# BMP280-Breakout_v11.net
KiCad netlist of a schematic drawn in EAGLE
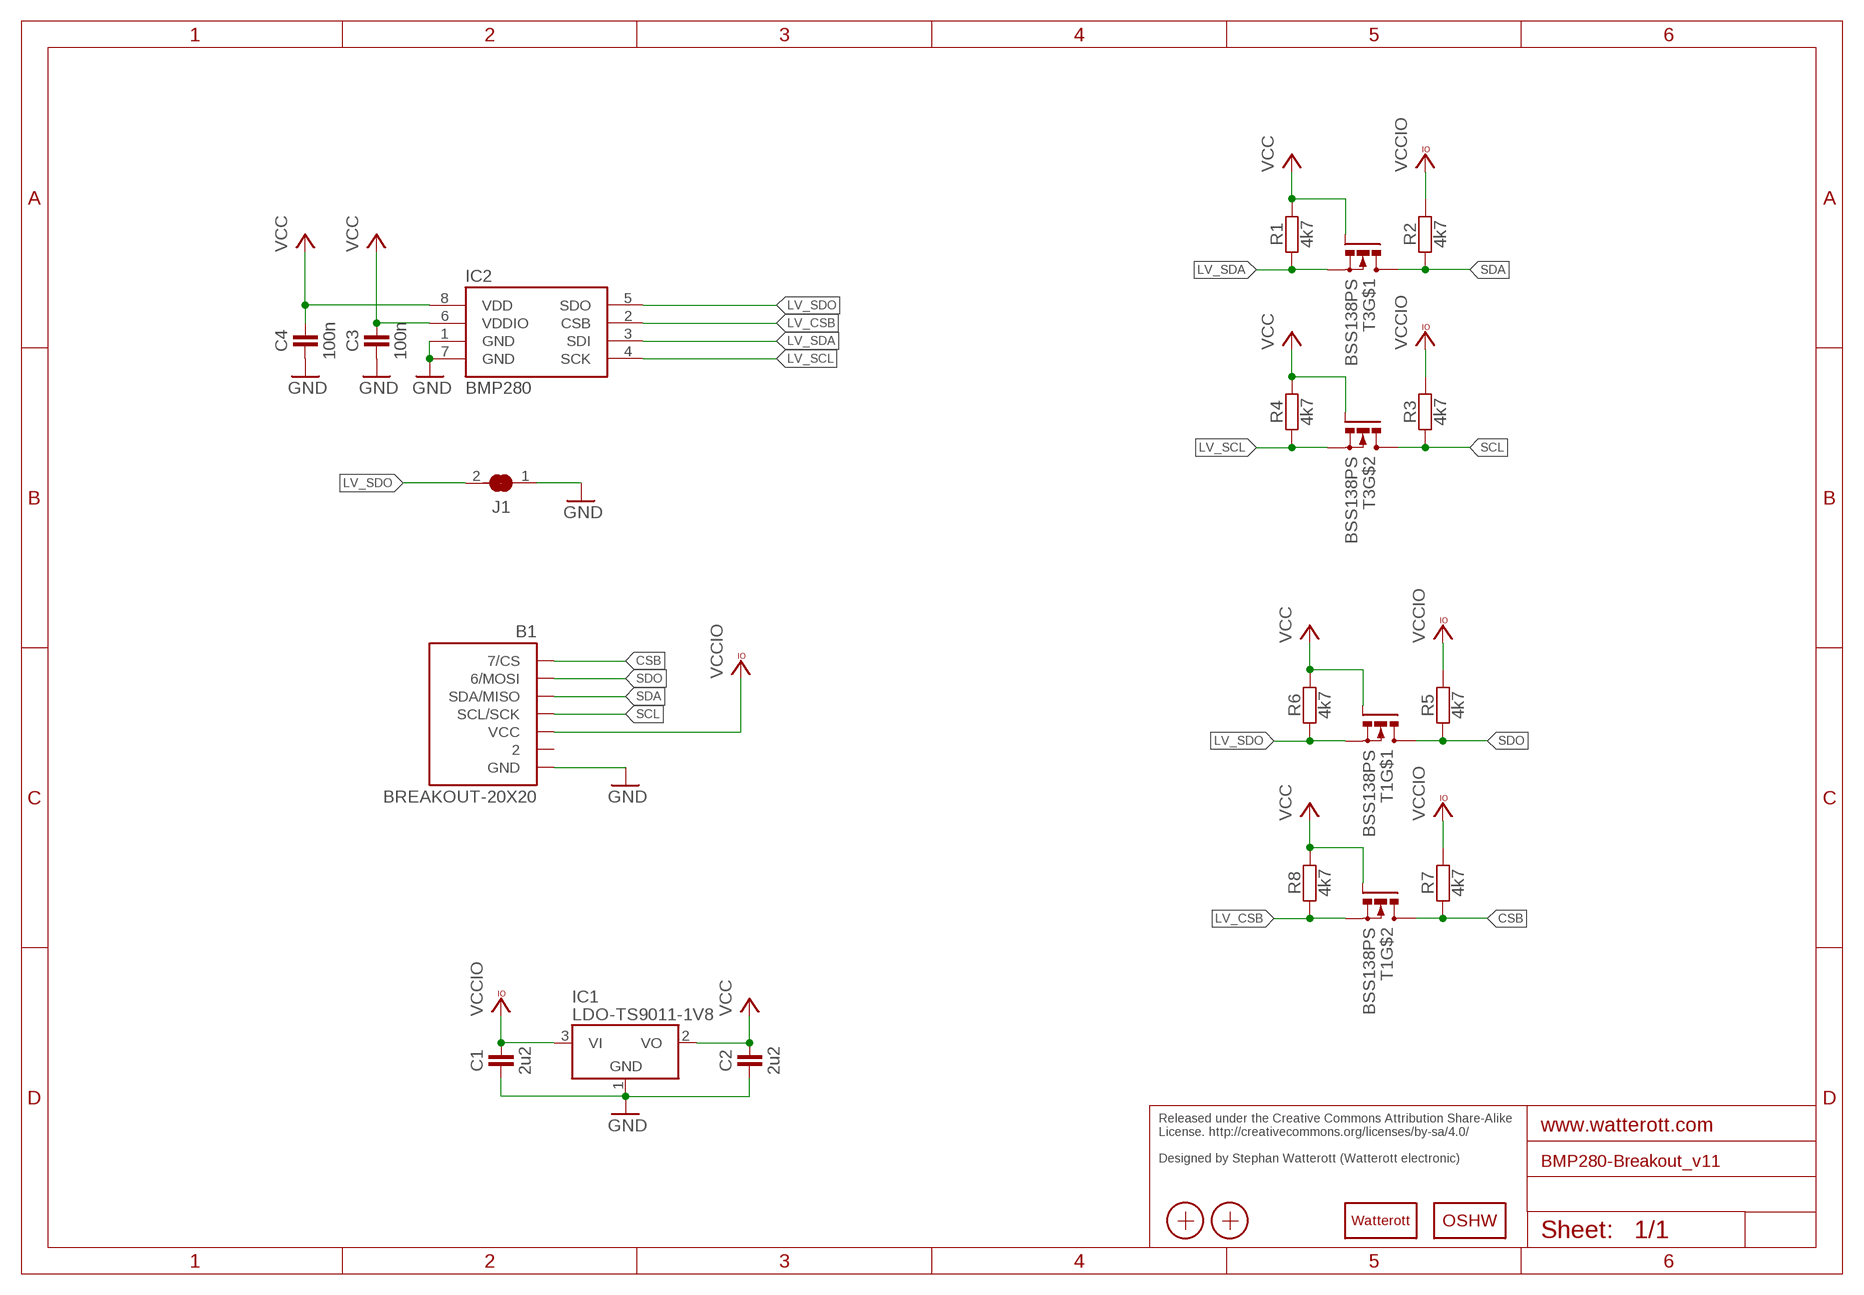
[diagram p0: schematic, sheet 1]

(export (version "E")
  (design (tool "Eeschema 10.0.6"))
  (components
    (comp (ref "B1")
      (value "BREAKOUT-20X20")
      (footprint "eagle-import:BREAKOUT-20X20")
      (libsource (lib "eagle-import") (part "BREAKOUT-20X20"))
    )
    (comp (ref "C1")
      (value "2u2")
      (footprint "eagle-import:R0402")
      (libsource (lib "eagle-import") (part "CAPACITOR-C0402"))
    )
    (comp (ref "C2")
      (value "2u2")
      (footprint "eagle-import:R0402")
      (libsource (lib "eagle-import") (part "CAPACITOR-C0402"))
    )
    (comp (ref "C3")
      (value "100n")
      (footprint "eagle-import:R0402")
      (libsource (lib "eagle-import") (part "CAPACITOR-C0402"))
    )
    (comp (ref "C4")
      (value "100n")
      (footprint "eagle-import:R0402")
      (libsource (lib "eagle-import") (part "CAPACITOR-C0402"))
    )
    (comp (ref "IC1")
      (value "LDO-TS9011-1V8")
      (footprint "eagle-import:SOT23")
      (libsource (lib "eagle-import") (part "LDO-TS9011-3V3"))
    )
    (comp (ref "IC2")
      (value "BMP280")
      (footprint "eagle-import:LGA")
      (libsource (lib "eagle-import") (part "BMP280"))
    )
    (comp (ref "J1")
      (value "JUMPER2")
      (footprint "eagle-import:JUMPER2")
      (libsource (lib "eagle-import") (part "JUMPER2"))
    )
    (comp (ref "LOGO1")
      (value "LOGO-S_PLACE_M")
      (footprint "eagle-import:SPARK_TPLACE_M")
      (libsource (lib "eagle-import") (part "LOGO-S_PLACE_M"))
    )
    (comp (ref "LOGO2")
      (value "OSHW_LOGOX0070")
      (footprint "eagle-import:OSHW_6X70")
      (libsource (lib "eagle-import") (part "OSHW_LOGOX0070"))
    )
    (comp (ref "R1")
      (value "4k7")
      (footprint "eagle-import:R0402")
      (libsource (lib "eagle-import") (part "RESISTOR-R0402"))
    )
    (comp (ref "R2")
      (value "4k7")
      (footprint "eagle-import:R0402")
      (libsource (lib "eagle-import") (part "RESISTOR-R0402"))
    )
    (comp (ref "R3")
      (value "4k7")
      (footprint "eagle-import:R0402")
      (libsource (lib "eagle-import") (part "RESISTOR-R0402"))
    )
    (comp (ref "R4")
      (value "4k7")
      (footprint "eagle-import:R0402")
      (libsource (lib "eagle-import") (part "RESISTOR-R0402"))
    )
    (comp (ref "R5")
      (value "4k7")
      (footprint "eagle-import:R0402")
      (libsource (lib "eagle-import") (part "RESISTOR-R0402"))
    )
    (comp (ref "R6")
      (value "4k7")
      (footprint "eagle-import:R0402")
      (libsource (lib "eagle-import") (part "RESISTOR-R0402"))
    )
    (comp (ref "R7")
      (value "4k7")
      (footprint "eagle-import:R0402")
      (libsource (lib "eagle-import") (part "RESISTOR-R0402"))
    )
    (comp (ref "R8")
      (value "4k7")
      (footprint "eagle-import:R0402")
      (libsource (lib "eagle-import") (part "RESISTOR-R0402"))
    )
    (comp (ref "T1")
      (value "BSS138PS")
      (footprint "eagle-import:SOT363")
      (libsource (lib "eagle-import") (part "BSS138PS"))
    )
    (comp (ref "T3")
      (value "BSS138PS")
      (footprint "eagle-import:SOT363")
      (libsource (lib "eagle-import") (part "BSS138PS"))
    )
    (comp (ref "X1")
      (value "PASSER-07")
      (footprint "eagle-import:PASSER_07MM")
      (libsource (lib "eagle-import") (part "PASSER-07"))
    )
    (comp (ref "X2")
      (value "PASSER-07")
      (footprint "eagle-import:PASSER_07MM")
      (libsource (lib "eagle-import") (part "PASSER-07"))
    )
  )
  (nets
    (net (code "1") (name "CSB") (class "Default")
      (node (ref "B1") (pin "CS") (pinfunction "7/CS_CS") (pintype "bidirectional"))
      (node (ref "R7") (pin "1") (pinfunction "1_1") (pintype "passive"))
      (node (ref "T1") (pin "3") (pinfunction "D_3") (pintype "passive"))
    )
    (net (code "2") (name "GND") (class "Default")
      (node (ref "B1") (pin "GND") (pinfunction "GND_GND") (pintype "power_in"))
      (node (ref "C1") (pin "1") (pinfunction "1_1") (pintype "passive"))
      (node (ref "C2") (pin "1") (pinfunction "1_1") (pintype "passive"))
      (node (ref "C3") (pin "1") (pinfunction "1_1") (pintype "passive"))
      (node (ref "C4") (pin "1") (pinfunction "1_1") (pintype "passive"))
      (node (ref "IC1") (pin "1") (pinfunction "GND_1") (pintype "passive"))
      (node (ref "IC2") (pin "1") (pinfunction "GND_1") (pintype "power_in"))
      (node (ref "IC2") (pin "7") (pinfunction "GND_7") (pintype "power_in"))
      (node (ref "J1") (pin "1") (pinfunction "1_1") (pintype "passive"))
    )
    (net (code "3") (name "LV_CSB") (class "Default")
      (node (ref "IC2") (pin "2") (pinfunction "CSB_2") (pintype "input"))
      (node (ref "R8") (pin "1") (pinfunction "1_1") (pintype "passive"))
      (node (ref "T1") (pin "4") (pinfunction "S_4") (pintype "passive"))
    )
    (net (code "4") (name "LV_SCL") (class "Default")
      (node (ref "IC2") (pin "4") (pinfunction "SCK_4") (pintype "input"))
      (node (ref "R4") (pin "1") (pinfunction "1_1") (pintype "passive"))
      (node (ref "T3") (pin "4") (pinfunction "S_4") (pintype "passive"))
    )
    (net (code "5") (name "LV_SDA") (class "Default")
      (node (ref "IC2") (pin "3") (pinfunction "SDI_3") (pintype "bidirectional"))
      (node (ref "R1") (pin "1") (pinfunction "1_1") (pintype "passive"))
      (node (ref "T3") (pin "1") (pinfunction "S_1") (pintype "passive"))
    )
    (net (code "6") (name "LV_SDO") (class "Default")
      (node (ref "IC2") (pin "5") (pinfunction "SDO_5") (pintype "bidirectional"))
      (node (ref "J1") (pin "2") (pinfunction "2_2") (pintype "passive"))
      (node (ref "R6") (pin "1") (pinfunction "1_1") (pintype "passive"))
      (node (ref "T1") (pin "1") (pinfunction "S_1") (pintype "passive"))
    )
    (net (code "7") (name "SCL") (class "Default")
      (node (ref "B1") (pin "SCL/SCK") (pinfunction "SCL/SCK_SCL/SCK") (pintype "bidirectional"))
      (node (ref "R3") (pin "1") (pinfunction "1_1") (pintype "passive"))
      (node (ref "T3") (pin "3") (pinfunction "D_3") (pintype "passive"))
    )
    (net (code "8") (name "SDA") (class "Default")
      (node (ref "B1") (pin "SDA/MISO") (pinfunction "SDA/MISO_SDA/MISO") (pintype "bidirectional"))
      (node (ref "R2") (pin "1") (pinfunction "1_1") (pintype "passive"))
      (node (ref "T3") (pin "6") (pinfunction "D_6") (pintype "passive"))
    )
    (net (code "9") (name "SDO") (class "Default")
      (node (ref "B1") (pin "MOSI") (pinfunction "6/MOSI_MOSI") (pintype "bidirectional"))
      (node (ref "R5") (pin "1") (pinfunction "1_1") (pintype "passive"))
      (node (ref "T1") (pin "6") (pinfunction "D_6") (pintype "passive"))
    )
    (net (code "10") (name "VCC") (class "Default")
      (node (ref "C2") (pin "2") (pinfunction "2_2") (pintype "passive"))
      (node (ref "C3") (pin "2") (pinfunction "2_2") (pintype "passive"))
      (node (ref "C4") (pin "2") (pinfunction "2_2") (pintype "passive"))
      (node (ref "IC1") (pin "2") (pinfunction "VO_2") (pintype "passive"))
      (node (ref "IC2") (pin "6") (pinfunction "VDDIO_6") (pintype "input"))
      (node (ref "IC2") (pin "8") (pinfunction "VDD_8") (pintype "power_in"))
      (node (ref "R1") (pin "2") (pinfunction "2_2") (pintype "passive"))
      (node (ref "R4") (pin "2") (pinfunction "2_2") (pintype "passive"))
      (node (ref "R6") (pin "2") (pinfunction "2_2") (pintype "passive"))
      (node (ref "R8") (pin "2") (pinfunction "2_2") (pintype "passive"))
      (node (ref "T1") (pin "2") (pinfunction "G_2") (pintype "passive"))
      (node (ref "T1") (pin "5") (pinfunction "G_5") (pintype "passive"))
      (node (ref "T3") (pin "2") (pinfunction "G_2") (pintype "passive"))
      (node (ref "T3") (pin "5") (pinfunction "G_5") (pintype "passive"))
    )
    (net (code "11") (name "VCCIO") (class "Default")
      (node (ref "B1") (pin "VCC") (pinfunction "VCC_VCC") (pintype "power_in"))
      (node (ref "C1") (pin "2") (pinfunction "2_2") (pintype "passive"))
      (node (ref "IC1") (pin "3") (pinfunction "VI_3") (pintype "input"))
      (node (ref "R2") (pin "2") (pinfunction "2_2") (pintype "passive"))
      (node (ref "R3") (pin "2") (pinfunction "2_2") (pintype "passive"))
      (node (ref "R5") (pin "2") (pinfunction "2_2") (pintype "passive"))
      (node (ref "R7") (pin "2") (pinfunction "2_2") (pintype "passive"))
    )
    (net (code "12") (name "unconnected-(B1-Pad2)") (class "Default")
      (node (ref "B1") (pin "2") (pinfunction "2_2") (pintype "bidirectional"))
    )
  )
)
